# RFIDv1.net
KiCad netlist of a schematic drawn in Altium Designer
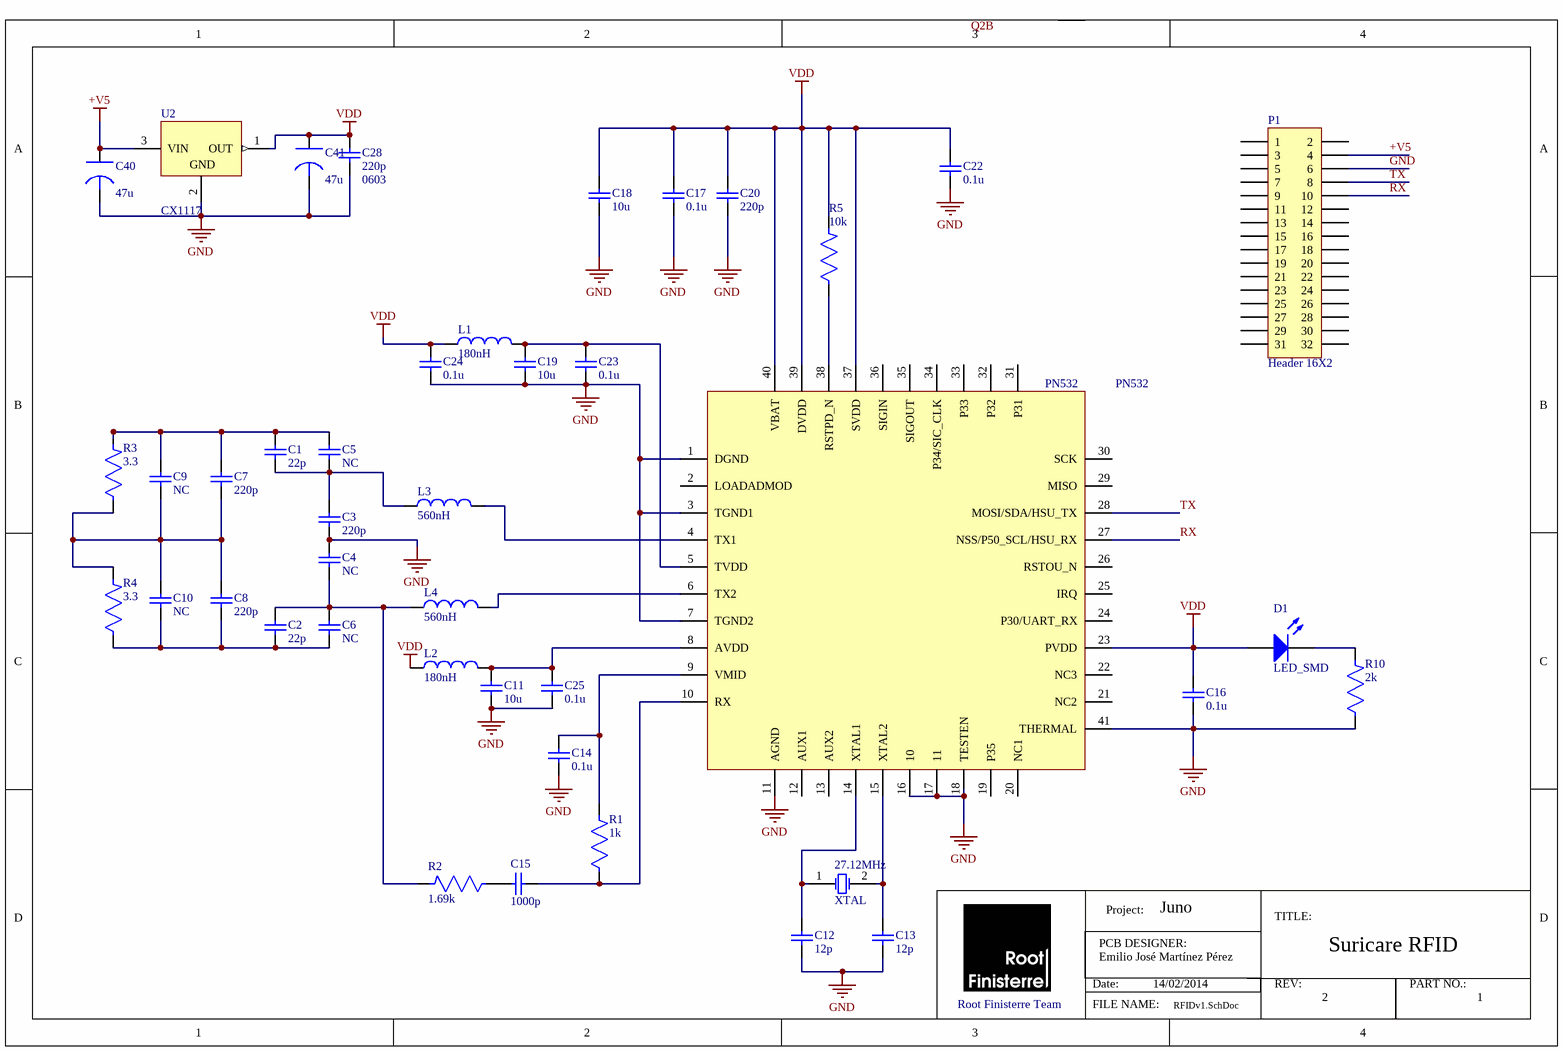
[diagram p0: RFIDv1.SchDoc]

(export (version "E")
  (design (tool "Eeschema 10.0.6"))
  (components
    (comp (ref "27.12MHz")
      (value "XTAL")
      (footprint "Crystal SMD")
      (description "Crystal Oscillator")
      (fields (field (name "PUBLISHER") "Altium Limited"))
      (libsource (lib "EMPv2_SCH") (part "XTAL"))
    )
    (comp (ref "C1")
      (value "22p")
      (footprint "0805")
      (description "Capacitor")
      (fields (field (name "PUBLISHER") "Altium Limited"))
      (libsource (lib "EMPv2_SCH") (part "CAP_1"))
    )
    (comp (ref "C2")
      (value "22p")
      (footprint "0805")
      (description "Capacitor")
      (fields (field (name "PUBLISHER") "Altium Limited"))
      (libsource (lib "EMPv2_SCH") (part "CAP_1"))
    )
    (comp (ref "C3")
      (value "220p")
      (footprint "0805")
      (description "Capacitor")
      (fields (field (name "PUBLISHER") "Altium Limited"))
      (libsource (lib "EMPv2_SCH") (part "CAP_1"))
    )
    (comp (ref "C4")
      (value "NC")
      (footprint "0805")
      (description "Capacitor")
      (fields (field (name "PUBLISHER") "Altium Limited"))
      (libsource (lib "EMPv2_SCH") (part "CAP_1"))
    )
    (comp (ref "C5")
      (value "NC")
      (footprint "0805")
      (description "Capacitor")
      (fields (field (name "PUBLISHER") "Altium Limited"))
      (libsource (lib "EMPv2_SCH") (part "CAP_1"))
    )
    (comp (ref "C6")
      (value "NC")
      (footprint "0805")
      (description "Capacitor")
      (fields (field (name "PUBLISHER") "Altium Limited"))
      (libsource (lib "EMPv2_SCH") (part "CAP_1"))
    )
    (comp (ref "C7")
      (value "220p")
      (footprint "0805")
      (description "Capacitor")
      (fields (field (name "PUBLISHER") "Altium Limited"))
      (libsource (lib "EMPv2_SCH") (part "CAP_1"))
    )
    (comp (ref "C8")
      (value "220p")
      (footprint "0805")
      (description "Capacitor")
      (fields (field (name "PUBLISHER") "Altium Limited"))
      (libsource (lib "EMPv2_SCH") (part "CAP_1"))
    )
    (comp (ref "C9")
      (value "NC")
      (footprint "0805")
      (description "Capacitor")
      (fields (field (name "PUBLISHER") "Altium Limited"))
      (libsource (lib "EMPv2_SCH") (part "CAP_1"))
    )
    (comp (ref "C10")
      (value "NC")
      (footprint "0805")
      (description "Capacitor")
      (fields (field (name "PUBLISHER") "Altium Limited"))
      (libsource (lib "EMPv2_SCH") (part "CAP_1"))
    )
    (comp (ref "C11")
      (value "10u")
      (footprint "0805")
      (description "Capacitor")
      (fields (field (name "PUBLISHER") "Altium Limited"))
      (libsource (lib "EMPv2_SCH") (part "CAP_1"))
    )
    (comp (ref "C12")
      (value "12p")
      (footprint "0805")
      (description "Capacitor")
      (fields (field (name "PUBLISHER") "Altium Limited"))
      (libsource (lib "EMPv2_SCH") (part "CAP_1"))
    )
    (comp (ref "C13")
      (value "12p")
      (footprint "0805")
      (description "Capacitor")
      (fields (field (name "PUBLISHER") "Altium Limited"))
      (libsource (lib "EMPv2_SCH") (part "CAP_1"))
    )
    (comp (ref "C14")
      (value "0.1u")
      (footprint "0805")
      (description "Capacitor")
      (fields (field (name "PUBLISHER") "Altium Limited"))
      (libsource (lib "EMPv2_SCH") (part "CAP_1"))
    )
    (comp (ref "C15")
      (value "1000p")
      (footprint "0805")
      (description "Capacitor")
      (fields (field (name "PUBLISHER") "Altium Limited"))
      (libsource (lib "EMPv2_SCH") (part "CAP_1"))
    )
    (comp (ref "C16")
      (value "0.1u")
      (footprint "0805")
      (description "Capacitor")
      (fields (field (name "PUBLISHER") "Altium Limited"))
      (libsource (lib "EMPv2_SCH") (part "CAP_1"))
    )
    (comp (ref "C17")
      (value "0.1u")
      (footprint "0805")
      (description "Capacitor")
      (fields (field (name "PUBLISHER") "Altium Limited"))
      (libsource (lib "EMPv2_SCH") (part "CAP_1"))
    )
    (comp (ref "C18")
      (value "10u")
      (footprint "0805")
      (description "Capacitor")
      (fields (field (name "PUBLISHER") "Altium Limited"))
      (libsource (lib "EMPv2_SCH") (part "CAP_1"))
    )
    (comp (ref "C19")
      (value "10u")
      (footprint "0805")
      (description "Capacitor")
      (fields (field (name "PUBLISHER") "Altium Limited"))
      (libsource (lib "EMPv2_SCH") (part "CAP_1"))
    )
    (comp (ref "C20")
      (value "220p")
      (footprint "0805")
      (description "Capacitor")
      (fields (field (name "Comment") "CAP") (field (name "PUBLISHER") "Altium Limited"))
      (libsource (lib "EMPv2_SCH") (part "CAP_1"))
    )
    (comp (ref "C22")
      (value "0.1u")
      (footprint "0805")
      (description "Capacitor")
      (fields (field (name "PUBLISHER") "Altium Limited"))
      (libsource (lib "EMPv2_SCH") (part "CAP_1"))
    )
    (comp (ref "C23")
      (value "0.1u")
      (footprint "0805")
      (description "Capacitor")
      (fields (field (name "PUBLISHER") "Altium Limited"))
      (libsource (lib "EMPv2_SCH") (part "CAP_1"))
    )
    (comp (ref "C24")
      (value "0.1u")
      (footprint "0805")
      (description "Capacitor")
      (fields (field (name "PUBLISHER") "Altium Limited"))
      (libsource (lib "EMPv2_SCH") (part "CAP_1"))
    )
    (comp (ref "C25")
      (value "0.1u")
      (footprint "0805")
      (description "Capacitor")
      (fields (field (name "PUBLISHER") "Altium Limited"))
      (libsource (lib "EMPv2_SCH") (part "CAP_1"))
    )
    (comp (ref "C28")
      (value "220p")
      (footprint "0603")
      (description "Capacitor")
      (fields (field (name "Comment") "CAP") (field (name "PUBLISHER") "Altium Limited"))
      (libsource (lib "EMPv2_SCH") (part "CAP_1"))
    )
    (comp (ref "C40")
      (value "47u")
      (footprint "CAPAE-G")
      (description "Condensador Electrolítico")
      (fields
        (field (name "PART NUMBER") "EMV-6R3ADA102MJA0G")
        (field (name "TOLERANCE") "20%")
        (field (name "AUTHOR") "Jaime Jiménez Ortega")
      )
      (libsource (lib "Inner_PCB_V05") (part "COND_ELEC_1"))
    )
    (comp (ref "C41")
      (value "47u")
      (footprint "CAPAE-G")
      (description "Condensador Electrolítico")
      (fields
        (field (name "PART NUMBER") "EMV-6R3ADA102MJA0G")
        (field (name "TOLERANCE") "20%")
        (field (name "AUTHOR") "Jaime Jiménez Ortega")
      )
      (libsource (lib "Inner_PCB_V05") (part "COND_ELEC_1"))
    )
    (comp (ref "D1")
      (value "LED_SMD")
      (footprint "LED0805_GREEN")
      (description "LED SMD")
      (fields (field (name "PUBLISHER") "Altium Limited"))
      (libsource (lib "EMPv2_SCH") (part "LED_SMD"))
    )
    (comp (ref "L1")
      (value "180nH")
      (footprint "INDC1608L")
      (description "Inductor")
      (fields (field (name "PUBLISHER") "Altium Limited"))
      (libsource (lib "EMPv2_SCH") (part "Inductor"))
    )
    (comp (ref "L2")
      (value "180nH")
      (footprint "INDC1608L")
      (description "Inductor")
      (fields (field (name "PUBLISHER") "Altium Limited"))
      (libsource (lib "EMPv2_SCH") (part "Inductor"))
    )
    (comp (ref "L3")
      (value "560nH")
      (footprint "0603")
      (description "Inductor")
      (fields (field (name "PUBLISHER") "Altium Limited"))
      (libsource (lib "EMPv2_SCH") (part "Inductor"))
    )
    (comp (ref "L4")
      (value "560nH")
      (footprint "INDC1608L")
      (description "Inductor")
      (fields (field (name "PUBLISHER") "Altium Limited"))
      (libsource (lib "EMPv2_SCH") (part "Inductor"))
    )
    (comp (ref "P1")
      (value "Header 16X2")
      (footprint "Miscellaneous Connectors:HDR2X16")
      (description "Header, 16-Pin, Dual row")
      (fields (field (name "PUBLISHER") "Altium Limited"))
      (libsource (lib "Miscellaneous Connectors") (part "Header 16X2"))
    )
    (comp (ref "PN532") (value "PN532") (footprint "PN532") (libsource (lib "EMPv2_SCH") (part "PN532")))
    (comp (ref "R1")
      (value "1k")
      (footprint "0805")
      (description "Resistencia")
      (fields (field (name "AUTHOR") "Jaime Jiménez Ortega"))
      (libsource (lib "EMPv2_SCH") (part "RES_1"))
    )
    (comp (ref "R2")
      (value "1.69k")
      (footprint "0805")
      (description "Resistencia")
      (fields (field (name "AUTHOR") "Jaime Jiménez Ortega"))
      (libsource (lib "EMPv2_SCH") (part "RES_1"))
    )
    (comp (ref "R3")
      (value "3.3")
      (footprint "0805")
      (description "Resistencia")
      (fields (field (name "AUTHOR") "Jaime Jiménez Ortega"))
      (libsource (lib "EMPv2_SCH") (part "RES_1"))
    )
    (comp (ref "R4")
      (value "3.3")
      (footprint "0805")
      (description "Resistencia")
      (fields (field (name "AUTHOR") "Jaime Jiménez Ortega"))
      (libsource (lib "EMPv2_SCH") (part "RES_1"))
    )
    (comp (ref "R5")
      (value "10k")
      (footprint "0805")
      (description "Resistencia")
      (fields (field (name "AUTHOR") "Jaime Jiménez Ortega"))
      (libsource (lib "EMPv2_SCH") (part "RES_1"))
    )
    (comp (ref "R10")
      (value "2k")
      (footprint "0805")
      (description "Resistencia")
      (fields (field (name "AUTHOR") "Jaime Jiménez Ortega"))
      (libsource (lib "EMPv2_SCH") (part "RES_1"))
    )
    (comp (ref "U2")
      (value "CX1117")
      (footprint "Raspberry_Rev2_V01:SOT223")
      (description "adjustable  and fixed voltage regulator")
      (fields (field (name "MANUFACTURER") "Silicon Cores Manuf."))
      (libsource (lib "EMPv2_SCH") (part "CX1117"))
    )
  )
  (nets
    (net (code "1") (name "+V5") (class "Default")
      (node (ref "C40") (pin "1") (pintype "power_in"))
      (node (ref "P1") (pin "4") (pinfunction "4_4") (pintype "passive"))
      (node (ref "U2") (pin "3") (pinfunction "VIN_3") (pintype "power_in"))
    )
    (net (code "3") (name "/RX") (class "Default")
      (node (ref "P1") (pin "10") (pinfunction "10_10") (pintype "passive"))
      (node (ref "PN532") (pin "27") (pinfunction "NSS/P50_SCL/HSU_RX_27") (pintype "passive"))
    )
    (net (code "4") (name "/TX") (class "Default")
      (node (ref "P1") (pin "8") (pinfunction "8_8") (pintype "passive"))
      (node (ref "PN532") (pin "28") (pinfunction "MOSI/SDA/HSU_TX_28") (pintype "passive"))
    )
    (net (code "5") (name "GND") (class "Default")
      (node (ref "C11") (pin "1") (pinfunction "1_1") (pintype "passive"))
      (node (ref "C12") (pin "1") (pinfunction "1_1") (pintype "passive"))
      (node (ref "C13") (pin "1") (pinfunction "1_1") (pintype "passive"))
      (node (ref "C14") (pin "1") (pinfunction "1_1") (pintype "passive"))
      (node (ref "C16") (pin "2") (pinfunction "2_2") (pintype "passive"))
      (node (ref "C17") (pin "2") (pinfunction "2_2") (pintype "passive"))
      (node (ref "C18") (pin "2") (pinfunction "2_2") (pintype "passive"))
      (node (ref "C19") (pin "2") (pinfunction "2_2") (pintype "passive"))
      (node (ref "C20") (pin "2") (pinfunction "2_2") (pintype "passive"))
      (node (ref "C22") (pin "2") (pinfunction "2_2") (pintype "passive"))
      (node (ref "C23") (pin "2") (pinfunction "2_2") (pintype "passive"))
      (node (ref "C24") (pin "2") (pinfunction "2_2") (pintype "passive"))
      (node (ref "C25") (pin "2") (pinfunction "2_2") (pintype "passive"))
      (node (ref "C28") (pin "2") (pinfunction "2_2") (pintype "passive"))
      (node (ref "C3") (pin "1") (pinfunction "1_1") (pintype "passive"))
      (node (ref "C4") (pin "2") (pinfunction "2_2") (pintype "passive"))
      (node (ref "C40") (pin "2") (pintype "power_in"))
      (node (ref "C41") (pin "2") (pintype "power_in"))
      (node (ref "P1") (pin "6") (pinfunction "6_6") (pintype "passive"))
      (node (ref "PN532") (pin "1") (pinfunction "DGND_1") (pintype "passive"))
      (node (ref "PN532") (pin "11") (pinfunction "AGND_11") (pintype "passive"))
      (node (ref "PN532") (pin "16") (pinfunction "10_16") (pintype "passive"))
      (node (ref "PN532") (pin "17") (pinfunction "11_17") (pintype "passive"))
      (node (ref "PN532") (pin "18") (pinfunction "TESTEN_18") (pintype "passive"))
      (node (ref "PN532") (pin "3") (pinfunction "TGND1_3") (pintype "passive"))
      (node (ref "PN532") (pin "41") (pinfunction "THERMAL_41") (pintype "passive"))
      (node (ref "PN532") (pin "7") (pinfunction "TGND2_7") (pintype "passive"))
      (node (ref "R10") (pin "1") (pintype "passive"))
      (node (ref "U2") (pin "2") (pinfunction "GND_2") (pintype "power_in"))
    )
    (net (code "6") (name "Net-(27.12MHz-OSC1)") (class "Default")
      (node (ref "27.12MHz") (pin "1") (pinfunction "OSC1_1") (pintype "passive"))
      (node (ref "C12") (pin "2") (pinfunction "2_2") (pintype "passive"))
      (node (ref "PN532") (pin "14") (pinfunction "XTAL1_14") (pintype "passive"))
    )
    (net (code "7") (name "Net-(27.12MHz-OSC2)") (class "Default")
      (node (ref "27.12MHz") (pin "2") (pinfunction "OSC2_2") (pintype "passive"))
      (node (ref "C13") (pin "2") (pinfunction "2_2") (pintype "passive"))
      (node (ref "PN532") (pin "15") (pinfunction "XTAL2_15") (pintype "passive"))
    )
    (net (code "8") (name "Net-(C1-Pad1)") (class "Default")
      (node (ref "C1") (pin "1") (pinfunction "1_1") (pintype "passive"))
      (node (ref "C3") (pin "2") (pinfunction "2_2") (pintype "passive"))
      (node (ref "C5") (pin "1") (pinfunction "1_1") (pintype "passive"))
      (node (ref "L3") (pin "1") (pinfunction "1_1") (pintype "passive"))
    )
    (net (code "9") (name "Net-(C1-Pad2)") (class "Default")
      (node (ref "C1") (pin "2") (pinfunction "2_2") (pintype "passive"))
      (node (ref "C5") (pin "2") (pinfunction "2_2") (pintype "passive"))
      (node (ref "C7") (pin "2") (pinfunction "2_2") (pintype "passive"))
      (node (ref "C9") (pin "2") (pinfunction "2_2") (pintype "passive"))
      (node (ref "R3") (pin "2") (pintype "passive"))
    )
    (net (code "10") (name "Net-(C2-Pad2)") (class "Default")
      (node (ref "C2") (pin "2") (pinfunction "2_2") (pintype "passive"))
      (node (ref "C4") (pin "1") (pinfunction "1_1") (pintype "passive"))
      (node (ref "C6") (pin "2") (pinfunction "2_2") (pintype "passive"))
      (node (ref "L4") (pin "1") (pinfunction "1_1") (pintype "passive"))
      (node (ref "R2") (pin "2") (pintype "passive"))
    )
    (net (code "11") (name "Net-(C10-Pad1)") (class "Default")
      (node (ref "C10") (pin "1") (pinfunction "1_1") (pintype "passive"))
      (node (ref "C2") (pin "1") (pinfunction "1_1") (pintype "passive"))
      (node (ref "C6") (pin "1") (pinfunction "1_1") (pintype "passive"))
      (node (ref "C8") (pin "1") (pinfunction "1_1") (pintype "passive"))
      (node (ref "R4") (pin "1") (pintype "passive"))
    )
    (net (code "12") (name "Net-(C10-Pad2)") (class "Default")
      (node (ref "C10") (pin "2") (pinfunction "2_2") (pintype "passive"))
      (node (ref "C7") (pin "1") (pinfunction "1_1") (pintype "passive"))
      (node (ref "C8") (pin "2") (pinfunction "2_2") (pintype "passive"))
      (node (ref "C9") (pin "1") (pinfunction "1_1") (pintype "passive"))
      (node (ref "R3") (pin "1") (pintype "passive"))
      (node (ref "R4") (pin "2") (pintype "passive"))
    )
    (net (code "13") (name "Net-(C15-Pad2)") (class "Default")
      (node (ref "C15") (pin "2") (pinfunction "2_2") (pintype "passive"))
      (node (ref "R2") (pin "1") (pintype "passive"))
    )
    (net (code "14") (name "Net-(D1-K)") (class "Default")
      (node (ref "D1") (pin "2") (pinfunction "K_2") (pintype "passive"))
      (node (ref "R10") (pin "2") (pintype "passive"))
    )
    (net (code "15") (name "Net-(PN532-AVDD)") (class "Default")
      (node (ref "C11") (pin "2") (pinfunction "2_2") (pintype "passive"))
      (node (ref "C25") (pin "1") (pinfunction "1_1") (pintype "passive"))
      (node (ref "L2") (pin "2") (pinfunction "2_2") (pintype "passive"))
      (node (ref "PN532") (pin "8") (pinfunction "AVDD_8") (pintype "passive"))
    )
    (net (code "16") (name "Net-(PN532-RSTPD_N)") (class "Default")
      (node (ref "PN532") (pin "38") (pinfunction "RSTPD_N_38") (pintype "passive"))
      (node (ref "R5") (pin "1") (pintype "passive"))
    )
    (net (code "17") (name "Net-(PN532-RX)") (class "Default")
      (node (ref "C15") (pin "1") (pinfunction "1_1") (pintype "passive"))
      (node (ref "PN532") (pin "10") (pinfunction "RX_10") (pintype "passive"))
      (node (ref "R1") (pin "1") (pintype "passive"))
    )
    (net (code "18") (name "Net-(PN532-TVDD)") (class "Default")
      (node (ref "C19") (pin "1") (pinfunction "1_1") (pintype "passive"))
      (node (ref "C23") (pin "1") (pinfunction "1_1") (pintype "passive"))
      (node (ref "L1") (pin "2") (pinfunction "2_2") (pintype "passive"))
      (node (ref "PN532") (pin "5") (pinfunction "TVDD_5") (pintype "passive"))
    )
    (net (code "19") (name "Net-(PN532-TX1)") (class "Default")
      (node (ref "L3") (pin "2") (pinfunction "2_2") (pintype "passive"))
      (node (ref "PN532") (pin "4") (pinfunction "TX1_4") (pintype "passive"))
    )
    (net (code "20") (name "Net-(PN532-TX2)") (class "Default")
      (node (ref "L4") (pin "2") (pinfunction "2_2") (pintype "passive"))
      (node (ref "PN532") (pin "6") (pinfunction "TX2_6") (pintype "passive"))
    )
    (net (code "21") (name "Net-(PN532-VMID)") (class "Default")
      (node (ref "C14") (pin "2") (pinfunction "2_2") (pintype "passive"))
      (node (ref "PN532") (pin "9") (pinfunction "VMID_9") (pintype "passive"))
      (node (ref "R1") (pin "2") (pintype "passive"))
    )
    (net (code "22") (name "VDD") (class "Default")
      (node (ref "C16") (pin "1") (pinfunction "1_1") (pintype "passive"))
      (node (ref "C17") (pin "1") (pinfunction "1_1") (pintype "passive"))
      (node (ref "C18") (pin "1") (pinfunction "1_1") (pintype "passive"))
      (node (ref "C20") (pin "1") (pinfunction "1_1") (pintype "passive"))
      (node (ref "C22") (pin "1") (pinfunction "1_1") (pintype "passive"))
      (node (ref "C24") (pin "1") (pinfunction "1_1") (pintype "passive"))
      (node (ref "C28") (pin "1") (pinfunction "1_1") (pintype "passive"))
      (node (ref "C41") (pin "1") (pintype "power_in"))
      (node (ref "D1") (pin "1") (pinfunction "A_1") (pintype "passive"))
      (node (ref "L1") (pin "1") (pinfunction "1_1") (pintype "passive"))
      (node (ref "L2") (pin "1") (pinfunction "1_1") (pintype "passive"))
      (node (ref "PN532") (pin "23") (pinfunction "PVDD_23") (pintype "passive"))
      (node (ref "PN532") (pin "37") (pinfunction "SVDD_37") (pintype "passive"))
      (node (ref "PN532") (pin "39") (pinfunction "DVDD_39") (pintype "passive"))
      (node (ref "PN532") (pin "40") (pinfunction "VBAT_40") (pintype "passive"))
      (node (ref "R5") (pin "2") (pintype "passive"))
      (node (ref "U2") (pin "1") (pinfunction "OUT_1") (pintype "output"))
    )
    (net (code "23") (name "unconnected-(P1-Pad1)") (class "Default")
      (node (ref "P1") (pin "1") (pinfunction "1_1") (pintype "passive"))
    )
    (net (code "24") (name "unconnected-(P1-Pad2)") (class "Default")
      (node (ref "P1") (pin "2") (pinfunction "2_2") (pintype "passive"))
    )
    (net (code "25") (name "unconnected-(P1-Pad3)") (class "Default")
      (node (ref "P1") (pin "3") (pinfunction "3_3") (pintype "passive"))
    )
    (net (code "26") (name "unconnected-(P1-Pad5)") (class "Default")
      (node (ref "P1") (pin "5") (pinfunction "5_5") (pintype "passive"))
    )
    (net (code "27") (name "unconnected-(P1-Pad7)") (class "Default")
      (node (ref "P1") (pin "7") (pinfunction "7_7") (pintype "passive"))
    )
    (net (code "28") (name "unconnected-(P1-Pad9)") (class "Default")
      (node (ref "P1") (pin "9") (pinfunction "9_9") (pintype "passive"))
    )
    (net (code "29") (name "unconnected-(P1-Pad11)") (class "Default")
      (node (ref "P1") (pin "11") (pinfunction "11_11") (pintype "passive"))
    )
    (net (code "30") (name "unconnected-(P1-Pad12)") (class "Default")
      (node (ref "P1") (pin "12") (pinfunction "12_12") (pintype "passive"))
    )
    (net (code "31") (name "unconnected-(P1-Pad13)") (class "Default")
      (node (ref "P1") (pin "13") (pinfunction "13_13") (pintype "passive"))
    )
    (net (code "32") (name "unconnected-(P1-Pad14)") (class "Default")
      (node (ref "P1") (pin "14") (pinfunction "14_14") (pintype "passive"))
    )
    (net (code "33") (name "unconnected-(P1-Pad15)") (class "Default")
      (node (ref "P1") (pin "15") (pinfunction "15_15") (pintype "passive"))
    )
    (net (code "34") (name "unconnected-(P1-Pad16)") (class "Default")
      (node (ref "P1") (pin "16") (pinfunction "16_16") (pintype "passive"))
    )
    (net (code "35") (name "unconnected-(P1-Pad17)") (class "Default")
      (node (ref "P1") (pin "17") (pinfunction "17_17") (pintype "passive"))
    )
    (net (code "36") (name "unconnected-(P1-Pad18)") (class "Default")
      (node (ref "P1") (pin "18") (pinfunction "18_18") (pintype "passive"))
    )
    (net (code "37") (name "unconnected-(P1-Pad19)") (class "Default")
      (node (ref "P1") (pin "19") (pinfunction "19_19") (pintype "passive"))
    )
    (net (code "38") (name "unconnected-(P1-Pad20)") (class "Default")
      (node (ref "P1") (pin "20") (pinfunction "20_20") (pintype "passive"))
    )
    (net (code "39") (name "unconnected-(P1-Pad21)") (class "Default")
      (node (ref "P1") (pin "21") (pinfunction "21_21") (pintype "passive"))
    )
    (net (code "40") (name "unconnected-(P1-Pad22)") (class "Default")
      (node (ref "P1") (pin "22") (pinfunction "22_22") (pintype "passive"))
    )
    (net (code "41") (name "unconnected-(P1-Pad23)") (class "Default")
      (node (ref "P1") (pin "23") (pinfunction "23_23") (pintype "passive"))
    )
    (net (code "42") (name "unconnected-(P1-Pad24)") (class "Default")
      (node (ref "P1") (pin "24") (pinfunction "24_24") (pintype "passive"))
    )
    (net (code "43") (name "unconnected-(P1-Pad25)") (class "Default")
      (node (ref "P1") (pin "25") (pinfunction "25_25") (pintype "passive"))
    )
    (net (code "44") (name "unconnected-(P1-Pad26)") (class "Default")
      (node (ref "P1") (pin "26") (pinfunction "26_26") (pintype "passive"))
    )
    (net (code "45") (name "unconnected-(P1-Pad27)") (class "Default")
      (node (ref "P1") (pin "27") (pinfunction "27_27") (pintype "passive"))
    )
    (net (code "46") (name "unconnected-(P1-Pad28)") (class "Default")
      (node (ref "P1") (pin "28") (pinfunction "28_28") (pintype "passive"))
    )
    (net (code "47") (name "unconnected-(P1-Pad29)") (class "Default")
      (node (ref "P1") (pin "29") (pinfunction "29_29") (pintype "passive"))
    )
    (net (code "48") (name "unconnected-(P1-Pad30)") (class "Default")
      (node (ref "P1") (pin "30") (pinfunction "30_30") (pintype "passive"))
    )
    (net (code "49") (name "unconnected-(P1-Pad31)") (class "Default")
      (node (ref "P1") (pin "31") (pinfunction "31_31") (pintype "passive"))
    )
    (net (code "50") (name "unconnected-(P1-Pad32)") (class "Default")
      (node (ref "P1") (pin "32") (pinfunction "32_32") (pintype "passive"))
    )
    (net (code "51") (name "unconnected-(PN532-AUX1-Pad12)") (class "Default")
      (node (ref "PN532") (pin "12") (pinfunction "AUX1_12") (pintype "passive"))
    )
    (net (code "52") (name "unconnected-(PN532-AUX2-Pad13)") (class "Default")
      (node (ref "PN532") (pin "13") (pinfunction "AUX2_13") (pintype "passive"))
    )
    (net (code "53") (name "unconnected-(PN532-IRQ-Pad25)") (class "Default")
      (node (ref "PN532") (pin "25") (pinfunction "IRQ_25") (pintype "passive"))
    )
    (net (code "54") (name "unconnected-(PN532-LOADADMOD-Pad2)") (class "Default")
      (node (ref "PN532") (pin "2") (pinfunction "LOADADMOD_2") (pintype "passive"))
    )
    (net (code "55") (name "unconnected-(PN532-MISO-Pad29)") (class "Default")
      (node (ref "PN532") (pin "29") (pinfunction "MISO_29") (pintype "passive"))
    )
    (net (code "56") (name "unconnected-(PN532-NC1-Pad20)") (class "Default")
      (node (ref "PN532") (pin "20") (pinfunction "NC1_20") (pintype "passive"))
    )
    (net (code "57") (name "unconnected-(PN532-NC2-Pad21)") (class "Default")
      (node (ref "PN532") (pin "21") (pinfunction "NC2_21") (pintype "passive"))
    )
    (net (code "58") (name "unconnected-(PN532-NC3-Pad22)") (class "Default")
      (node (ref "PN532") (pin "22") (pinfunction "NC3_22") (pintype "passive"))
    )
    (net (code "59") (name "unconnected-(PN532-P30{slash}UART_RX-Pad24)") (class "Default")
      (node (ref "PN532") (pin "24") (pinfunction "P30/UART_RX_24") (pintype "passive"))
    )
    (net (code "60") (name "unconnected-(PN532-P31-Pad31)") (class "Default")
      (node (ref "PN532") (pin "31") (pinfunction "P31_31") (pintype "passive"))
    )
    (net (code "61") (name "unconnected-(PN532-P32-Pad32)") (class "Default")
      (node (ref "PN532") (pin "32") (pinfunction "P32_32") (pintype "passive"))
    )
    (net (code "62") (name "unconnected-(PN532-P33-Pad33)") (class "Default")
      (node (ref "PN532") (pin "33") (pinfunction "P33_33") (pintype "passive"))
    )
    (net (code "63") (name "unconnected-(PN532-P34{slash}SIC_CLK-Pad34)") (class "Default")
      (node (ref "PN532") (pin "34") (pinfunction "P34/SIC_CLK_34") (pintype "passive"))
    )
    (net (code "64") (name "unconnected-(PN532-P35-Pad19)") (class "Default")
      (node (ref "PN532") (pin "19") (pinfunction "P35_19") (pintype "passive"))
    )
    (net (code "65") (name "unconnected-(PN532-RSTOU_N-Pad26)") (class "Default")
      (node (ref "PN532") (pin "26") (pinfunction "RSTOU_N_26") (pintype "passive"))
    )
    (net (code "66") (name "unconnected-(PN532-SCK-Pad30)") (class "Default")
      (node (ref "PN532") (pin "30") (pinfunction "SCK_30") (pintype "passive"))
    )
    (net (code "67") (name "unconnected-(PN532-SIGIN-Pad36)") (class "Default")
      (node (ref "PN532") (pin "36") (pinfunction "SIGIN_36") (pintype "passive"))
    )
    (net (code "68") (name "unconnected-(PN532-SIGOUT-Pad35)") (class "Default")
      (node (ref "PN532") (pin "35") (pinfunction "SIGOUT_35") (pintype "passive"))
    )
  )
)
